# triac.net
KiCad netlist of a schematic drawn in EAGLE
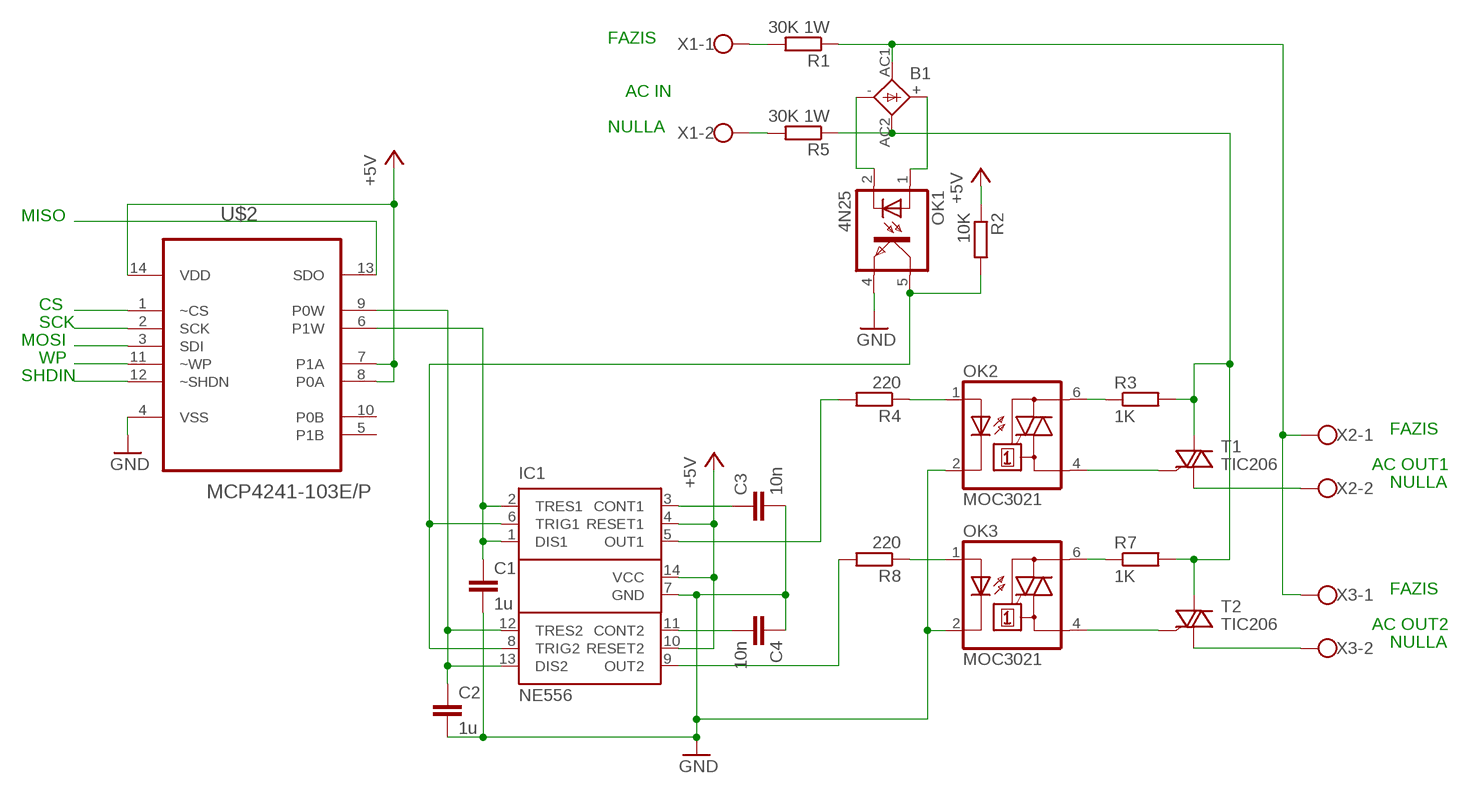
[diagram p0: schematic, sheet 1]

(export (version "E")
  (design (tool "Eeschema 10.0.6"))
  (components
    (comp (ref "B1")
      (value "2KBB")
      (footprint "eagle-import:2KBB")
      (libsource (lib "eagle-import") (part "2KBB"))
    )
    (comp (ref "C1")
      (value "1u")
      (footprint "eagle-import:C050-055X075")
      (libsource (lib "eagle-import") (part "C-EU050-055X075"))
    )
    (comp (ref "C2")
      (value "1u")
      (footprint "eagle-import:C050-055X075")
      (libsource (lib "eagle-import") (part "C-EU050-055X075"))
    )
    (comp (ref "C3")
      (value "10n")
      (footprint "eagle-import:C050-055X075")
      (libsource (lib "eagle-import") (part "C-EU050-055X075"))
    )
    (comp (ref "C4")
      (value "10n")
      (footprint "eagle-import:C050-055X075")
      (libsource (lib "eagle-import") (part "C-EU050-055X075"))
    )
    (comp (ref "IC1")
      (value "NE556")
      (footprint "eagle-import:DIL14")
      (libsource (lib "eagle-import") (part "NE556"))
    )
    (comp (ref "OK1")
      (value "4N25")
      (footprint "eagle-import:DIL06")
      (fields (field (name "MF") "VISHAY/TELEFUNKEN") (field (name "MPN") "CNY17F-3"))
      (libsource (lib "eagle-import") (part "CNY17F"))
    )
    (comp (ref "OK2")
      (value "MOC3021")
      (footprint "eagle-import:DIL06")
      (fields (field (name "MF") "FAIRCHILD SEMICONDUCTOR") (field (name "MPN") "MOC3031M"))
      (libsource (lib "eagle-import") (part "MOC3031M"))
    )
    (comp (ref "OK3")
      (value "MOC3021")
      (footprint "eagle-import:DIL06")
      (fields (field (name "MF") "FAIRCHILD SEMICONDUCTOR") (field (name "MPN") "MOC3031M"))
      (libsource (lib "eagle-import") (part "MOC3031M"))
    )
    (comp (ref "R1")
      (value "30K 1W")
      (footprint "eagle-import:0207_10")
      (libsource (lib "eagle-import") (part "R-EU_0207/10"))
    )
    (comp (ref "R2")
      (value "10K")
      (footprint "eagle-import:0207_10")
      (libsource (lib "eagle-import") (part "R-EU_0207/10"))
    )
    (comp (ref "R3")
      (value "1K")
      (footprint "eagle-import:0207_10")
      (libsource (lib "eagle-import") (part "R-EU_0207/10"))
    )
    (comp (ref "R4")
      (value "220")
      (footprint "eagle-import:0207_10")
      (libsource (lib "eagle-import") (part "R-EU_0207/10"))
    )
    (comp (ref "R5")
      (value "30K 1W")
      (footprint "eagle-import:0207_10")
      (libsource (lib "eagle-import") (part "R-EU_0207/10"))
    )
    (comp (ref "R7")
      (value "1K")
      (footprint "eagle-import:0207_10")
      (libsource (lib "eagle-import") (part "R-EU_0207/10"))
    )
    (comp (ref "R8")
      (value "220")
      (footprint "eagle-import:0207_10")
      (libsource (lib "eagle-import") (part "R-EU_0207/10"))
    )
    (comp (ref "T1")
      (value "TIC206")
      (footprint "eagle-import:TO220BH")
      (libsource (lib "eagle-import") (part "BT138-H"))
    )
    (comp (ref "T2")
      (value "TIC206")
      (footprint "eagle-import:TO220BH")
      (libsource (lib "eagle-import") (part "BT138-H"))
    )
    (comp (ref "U$2")
      (value "MCP4241-103E/P")
      (footprint "eagle-import:DIP254P762X533-14")
      (libsource (lib "eagle-import") (part "MCP4241-103E/P"))
    )
    (comp (ref "X1")
      (value "W237-102")
      (footprint "eagle-import:W237-102")
      (fields (field (name "MPN") "237-102"))
      (libsource (lib "eagle-import") (part "W237-102"))
    )
    (comp (ref "X2")
      (value "W237-102")
      (footprint "eagle-import:W237-102")
      (fields (field (name "MPN") "237-102"))
      (libsource (lib "eagle-import") (part "W237-102"))
    )
    (comp (ref "X3")
      (value "W237-102")
      (footprint "eagle-import:W237-102")
      (fields (field (name "MPN") "237-102"))
      (libsource (lib "eagle-import") (part "W237-102"))
    )
  )
  (nets
    (net (code "1") (name "+5V") (class "Default")
      (node (ref "IC1") (pin "10") (pinfunction "RESET2_10") (pintype "input"))
      (node (ref "IC1") (pin "14") (pinfunction "VCC_14") (pintype "power_in"))
      (node (ref "IC1") (pin "4") (pinfunction "RESET1_4") (pintype "input"))
      (node (ref "R2") (pin "1") (pinfunction "1_1") (pintype "passive"))
      (node (ref "U$2") (pin "14") (pinfunction "VDD_14") (pintype "power_in"))
      (node (ref "U$2") (pin "7") (pinfunction "P1A_7") (pintype "bidirectional"))
      (node (ref "U$2") (pin "8") (pinfunction "P0A_8") (pintype "bidirectional"))
    )
    (net (code "2") (name "GND") (class "Default")
      (node (ref "C1") (pin "2") (pinfunction "2_2") (pintype "passive"))
      (node (ref "C2") (pin "2") (pinfunction "2_2") (pintype "passive"))
      (node (ref "C3") (pin "2") (pinfunction "2_2") (pintype "passive"))
      (node (ref "C4") (pin "1") (pinfunction "1_1") (pintype "passive"))
      (node (ref "IC1") (pin "7") (pinfunction "GND_7") (pintype "power_in"))
      (node (ref "OK1") (pin "4") (pinfunction "EMIT_4") (pintype "passive"))
      (node (ref "OK2") (pin "2") (pinfunction "C_2") (pintype "passive"))
      (node (ref "OK3") (pin "2") (pinfunction "C_2") (pintype "passive"))
      (node (ref "U$2") (pin "4") (pinfunction "VSS_4") (pintype "power_in"))
    )
    (net (code "3") (name "Net-(IC1-CONT1)") (class "Default")
      (node (ref "C3") (pin "1") (pinfunction "1_1") (pintype "passive"))
      (node (ref "IC1") (pin "3") (pinfunction "CONT1_3") (pintype "input"))
    )
    (net (code "4") (name "Net-(IC1-CONT2)") (class "Default")
      (node (ref "C4") (pin "2") (pinfunction "2_2") (pintype "passive"))
      (node (ref "IC1") (pin "11") (pinfunction "CONT2_11") (pintype "input"))
    )
    (net (code "5") (name "Net-(IC1-DIS1)") (class "Default")
      (node (ref "C1") (pin "1") (pinfunction "1_1") (pintype "passive"))
      (node (ref "IC1") (pin "1") (pinfunction "DIS1_1") (pintype "input"))
      (node (ref "IC1") (pin "2") (pinfunction "TRES1_2") (pintype "input"))
      (node (ref "U$2") (pin "6") (pinfunction "P1W_6") (pintype "bidirectional"))
    )
    (net (code "6") (name "Net-(IC1-DIS2)") (class "Default")
      (node (ref "C2") (pin "1") (pinfunction "1_1") (pintype "passive"))
      (node (ref "IC1") (pin "12") (pinfunction "TRES2_12") (pintype "input"))
      (node (ref "IC1") (pin "13") (pinfunction "DIS2_13") (pintype "input"))
      (node (ref "U$2") (pin "9") (pinfunction "P0W_9") (pintype "bidirectional"))
    )
    (net (code "7") (name "Net-(IC1-OUT1)") (class "Default")
      (node (ref "IC1") (pin "5") (pinfunction "OUT1_5") (pintype "output"))
      (node (ref "R4") (pin "2") (pinfunction "2_2") (pintype "passive"))
    )
    (net (code "8") (name "Net-(IC1-OUT2)") (class "Default")
      (node (ref "IC1") (pin "9") (pinfunction "OUT2_9") (pintype "output"))
      (node (ref "R8") (pin "2") (pinfunction "2_2") (pintype "passive"))
    )
    (net (code "9") (name "Net-(IC1-TRIG1)") (class "Default")
      (node (ref "IC1") (pin "6") (pinfunction "TRIG1_6") (pintype "input"))
      (node (ref "IC1") (pin "8") (pinfunction "TRIG2_8") (pintype "input"))
      (node (ref "OK1") (pin "5") (pinfunction "COL_5") (pintype "passive"))
      (node (ref "R2") (pin "2") (pinfunction "2_2") (pintype "passive"))
    )
    (net (code "10") (name "Net-(OK1-A)") (class "Default")
      (node (ref "B1") (pin "+") (pinfunction "+_+") (pintype "passive"))
      (node (ref "OK1") (pin "1") (pinfunction "A_1") (pintype "passive"))
    )
    (net (code "11") (name "Net-(OK1-C)") (class "Default")
      (node (ref "B1") (pin "-") (pinfunction "-_-") (pintype "passive"))
      (node (ref "OK1") (pin "2") (pinfunction "C_2") (pintype "passive"))
    )
    (net (code "12") (name "Net-(OK2-A)") (class "Default")
      (node (ref "OK2") (pin "1") (pinfunction "A_1") (pintype "passive"))
      (node (ref "R4") (pin "1") (pinfunction "1_1") (pintype "passive"))
    )
    (net (code "13") (name "Net-(OK2-A1)") (class "Default")
      (node (ref "OK2") (pin "4") (pinfunction "A1_4") (pintype "passive"))
      (node (ref "T1") (pin "G") (pinfunction "G_G") (pintype "passive"))
    )
    (net (code "14") (name "Net-(OK2-A2)") (class "Default")
      (node (ref "OK2") (pin "6") (pinfunction "A2_6") (pintype "passive"))
      (node (ref "R3") (pin "1") (pinfunction "1_1") (pintype "passive"))
    )
    (net (code "15") (name "Net-(OK3-A)") (class "Default")
      (node (ref "OK3") (pin "1") (pinfunction "A_1") (pintype "passive"))
      (node (ref "R8") (pin "1") (pinfunction "1_1") (pintype "passive"))
    )
    (net (code "16") (name "Net-(OK3-A1)") (class "Default")
      (node (ref "OK3") (pin "4") (pinfunction "A1_4") (pintype "passive"))
      (node (ref "T2") (pin "G") (pinfunction "G_G") (pintype "passive"))
    )
    (net (code "17") (name "Net-(OK3-A2)") (class "Default")
      (node (ref "OK3") (pin "6") (pinfunction "A2_6") (pintype "passive"))
      (node (ref "R7") (pin "1") (pinfunction "1_1") (pintype "passive"))
    )
    (net (code "18") (name "Net-(T1-A1)") (class "Default")
      (node (ref "T1") (pin "T1") (pinfunction "A1_T1") (pintype "passive"))
      (node (ref "X2") (pin "2") (pinfunction "KL_2") (pintype "passive"))
    )
    (net (code "19") (name "Net-(T1-A2)") (class "Default")
      (node (ref "B1") (pin "AC2") (pinfunction "AC2_AC2") (pintype "passive"))
      (node (ref "R3") (pin "2") (pinfunction "2_2") (pintype "passive"))
      (node (ref "R5") (pin "1") (pinfunction "1_1") (pintype "passive"))
      (node (ref "R7") (pin "2") (pinfunction "2_2") (pintype "passive"))
      (node (ref "T1") (pin "T2") (pinfunction "A2_T2") (pintype "passive"))
      (node (ref "T2") (pin "T2") (pinfunction "A2_T2") (pintype "passive"))
    )
    (net (code "20") (name "Net-(T2-A1)") (class "Default")
      (node (ref "T2") (pin "T1") (pinfunction "A1_T1") (pintype "passive"))
      (node (ref "X3") (pin "2") (pinfunction "KL_2") (pintype "passive"))
    )
    (net (code "21") (name "Net-(X1A-KL)") (class "Default")
      (node (ref "R1") (pin "2") (pinfunction "2_2") (pintype "passive"))
      (node (ref "X1") (pin "1") (pinfunction "KL_1") (pintype "passive"))
    )
    (net (code "22") (name "Net-(X1B-KL)") (class "Default")
      (node (ref "R5") (pin "2") (pinfunction "2_2") (pintype "passive"))
      (node (ref "X1") (pin "2") (pinfunction "KL_2") (pintype "passive"))
    )
    (net (code "23") (name "Net-(X2A-KL)") (class "Default")
      (node (ref "B1") (pin "AC1") (pinfunction "AC1_AC1") (pintype "passive"))
      (node (ref "R1") (pin "1") (pinfunction "1_1") (pintype "passive"))
      (node (ref "X2") (pin "1") (pinfunction "KL_1") (pintype "passive"))
      (node (ref "X3") (pin "1") (pinfunction "KL_1") (pintype "passive"))
    )
    (net (code "24") (name "unconnected-(U$2-P0B-Pad10)") (class "Default")
      (node (ref "U$2") (pin "10") (pinfunction "P0B_10") (pintype "bidirectional"))
    )
    (net (code "25") (name "unconnected-(U$2-P1B-Pad5)") (class "Default")
      (node (ref "U$2") (pin "5") (pinfunction "P1B_5") (pintype "bidirectional"))
    )
    (net (code "26") (name "unconnected-(U$2-SCK-Pad2)") (class "Default")
      (node (ref "U$2") (pin "2") (pinfunction "SCK_2") (pintype "input"))
    )
    (net (code "27") (name "unconnected-(U$2-SDI-Pad3)") (class "Default")
      (node (ref "U$2") (pin "3") (pinfunction "SDI_3") (pintype "input"))
    )
    (net (code "28") (name "unconnected-(U$2-SDO-Pad13)") (class "Default")
      (node (ref "U$2") (pin "13") (pinfunction "SDO_13") (pintype "output"))
    )
    (net (code "29") (name "unconnected-(U$2-~{CS}-Pad1)") (class "Default")
      (node (ref "U$2") (pin "1") (pinfunction "~{CS}_1") (pintype "input"))
    )
    (net (code "30") (name "unconnected-(U$2-~{SHDN}-Pad12)") (class "Default")
      (node (ref "U$2") (pin "12") (pinfunction "~{SHDN}_12") (pintype "input"))
    )
    (net (code "31") (name "unconnected-(U$2-~{WP}-Pad11)") (class "Default")
      (node (ref "U$2") (pin "11") (pinfunction "~{WP}_11") (pintype "input"))
    )
  )
)
